# extender.net
KiCad netlist of a schematic drawn in Altium Designer
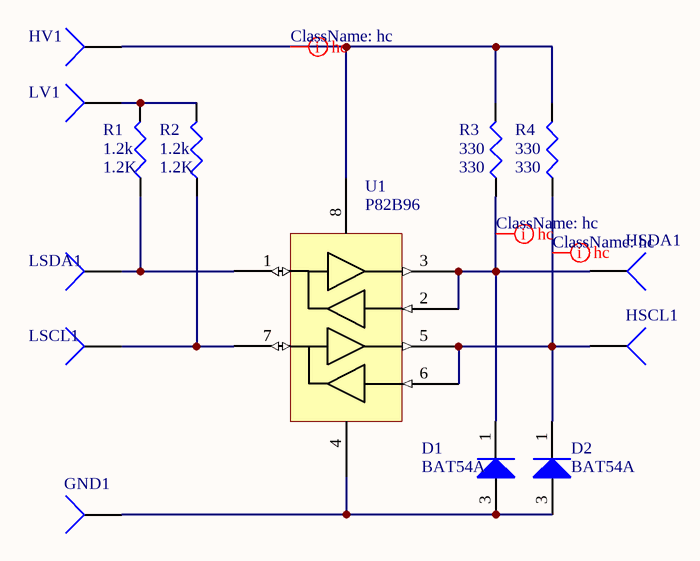
[diagram p0: extender.SchDoc]

(export (version "E")
  (design (tool "Eeschema 10.0.6"))
  (components
    (comp (ref "D1")
      (value "BAT54A")
      (footprint "SOT-23_N")
      (description "Default Diode")
      (fields (field (name "PUBLISHER") "Altium Limited"))
      (libsource (lib "Miscellaneous Devices") (part "Diode"))
    )
    (comp (ref "D2")
      (value "BAT54A")
      (footprint "SOT-23_N")
      (description "Default Diode")
      (fields (field (name "PUBLISHER") "Altium Limited"))
      (libsource (lib "Miscellaneous Devices") (part "Diode"))
    )
    (comp (ref "GND1")
      (value "GND")
      (footprint "PIN1")
      (description "Socket")
      (fields (field (name "PUBLISHER") "Altium Limited"))
      (libsource (lib "misc") (part "Socket"))
    )
    (comp (ref "HSCL1")
      (value "SCL")
      (footprint "PIN1")
      (description "Socket")
      (fields (field (name "PUBLISHER") "Altium Limited"))
      (libsource (lib "misc") (part "Socket"))
    )
    (comp (ref "HSDA1")
      (value "SDA")
      (footprint "PIN1")
      (description "Socket")
      (fields (field (name "PUBLISHER") "Altium Limited"))
      (libsource (lib "misc") (part "Socket"))
    )
    (comp (ref "HV1")
      (value "5V")
      (footprint "PIN1")
      (description "Socket")
      (fields (field (name "PUBLISHER") "Altium Limited"))
      (libsource (lib "misc") (part "Socket"))
    )
    (comp (ref "LSCL1")
      (value "SCL")
      (footprint "PIN1")
      (description "Socket")
      (fields (field (name "PUBLISHER") "Altium Limited"))
      (libsource (lib "misc") (part "Socket"))
    )
    (comp (ref "LSDA1")
      (value "SDA")
      (footprint "PIN1")
      (description "Socket")
      (fields (field (name "PUBLISHER") "Altium Limited"))
      (libsource (lib "misc") (part "Socket"))
    )
    (comp (ref "LV1")
      (value "5V")
      (footprint "PIN1")
      (description "Socket")
      (fields (field (name "PUBLISHER") "Altium Limited"))
      (libsource (lib "misc") (part "Socket"))
    )
    (comp (ref "R1")
      (value "1.2k")
      (footprint "J1-0603")
      (description "Resistor")
      (fields (field (name "ALTIUM_VALUE") "1.2K") (field (name "PUBLISHER") "Altium Limited"))
      (libsource (lib "Miscellaneous Devices") (part "Res3"))
    )
    (comp (ref "R2")
      (value "1.2k")
      (footprint "J1-0603")
      (description "Resistor")
      (fields (field (name "ALTIUM_VALUE") "1.2K") (field (name "PUBLISHER") "Altium Limited"))
      (libsource (lib "Miscellaneous Devices") (part "Res3"))
    )
    (comp (ref "R3")
      (value "330")
      (footprint "R1206")
      (description "Resistor")
      (fields (field (name "ALTIUM_VALUE") "330") (field (name "PUBLISHER") "Altium Limited"))
      (libsource (lib "Miscellaneous Devices") (part "Res3"))
    )
    (comp (ref "R4")
      (value "330")
      (footprint "R1206")
      (description "Resistor")
      (fields (field (name "ALTIUM_VALUE") "330") (field (name "PUBLISHER") "Altium Limited"))
      (libsource (lib "Miscellaneous Devices") (part "Res3"))
    )
    (comp (ref "U1") (value "P82B96") (footprint "8VSSOP") (libsource (lib "misc") (part "P82B96")))
  )
  (nets
    (net (code "1") (name "Net-(D1-A)") (class "Default")
      (node (ref "D1") (pin "3") (pinfunction "A_3") (pintype "passive"))
      (node (ref "D2") (pin "3") (pinfunction "A_3") (pintype "passive"))
      (node (ref "GND1") (pin "1") (pinfunction "1_1") (pintype "passive"))
      (node (ref "U1") (pin "4") (pinfunction "4_4") (pintype "passive"))
    )
    (net (code "2") (name "Net-(D1-K)") (class "Default")
      (node (ref "D1") (pin "1") (pinfunction "K_1") (pintype "passive"))
      (node (ref "HSDA1") (pin "1") (pinfunction "1_1") (pintype "passive"))
      (node (ref "R3") (pin "1") (pinfunction "1_1") (pintype "passive"))
      (node (ref "U1") (pin "2") (pinfunction "2_2") (pintype "input"))
      (node (ref "U1") (pin "3") (pinfunction "3_3") (pintype "output"))
    )
    (net (code "3") (name "Net-(D2-K)") (class "Default")
      (node (ref "D2") (pin "1") (pinfunction "K_1") (pintype "passive"))
      (node (ref "HSCL1") (pin "1") (pinfunction "1_1") (pintype "passive"))
      (node (ref "R4") (pin "1") (pinfunction "1_1") (pintype "passive"))
      (node (ref "U1") (pin "5") (pinfunction "5_5") (pintype "output"))
      (node (ref "U1") (pin "6") (pinfunction "6_6") (pintype "input"))
    )
    (net (code "4") (name "Net-(HV1-Pad1)") (class "Default")
      (node (ref "HV1") (pin "1") (pinfunction "1_1") (pintype "passive"))
      (node (ref "R3") (pin "2") (pinfunction "2_2") (pintype "passive"))
      (node (ref "R4") (pin "2") (pinfunction "2_2") (pintype "passive"))
      (node (ref "U1") (pin "8") (pinfunction "8_8") (pintype "passive"))
    )
    (net (code "5") (name "Net-(LSCL1-Pad1)") (class "Default")
      (node (ref "LSCL1") (pin "1") (pinfunction "1_1") (pintype "passive"))
      (node (ref "R2") (pin "1") (pinfunction "1_1") (pintype "passive"))
      (node (ref "U1") (pin "7") (pinfunction "7_7") (pintype "bidirectional"))
    )
    (net (code "6") (name "Net-(LSDA1-Pad1)") (class "Default")
      (node (ref "LSDA1") (pin "1") (pinfunction "1_1") (pintype "passive"))
      (node (ref "R1") (pin "1") (pinfunction "1_1") (pintype "passive"))
      (node (ref "U1") (pin "1") (pinfunction "1_1") (pintype "bidirectional"))
    )
    (net (code "7") (name "Net-(LV1-Pad1)") (class "Default")
      (node (ref "LV1") (pin "1") (pinfunction "1_1") (pintype "passive"))
      (node (ref "R1") (pin "2") (pinfunction "2_2") (pintype "passive"))
      (node (ref "R2") (pin "2") (pinfunction "2_2") (pintype "passive"))
    )
  )
)
